# Relay.net
KiCad netlist of a schematic drawn in EAGLE
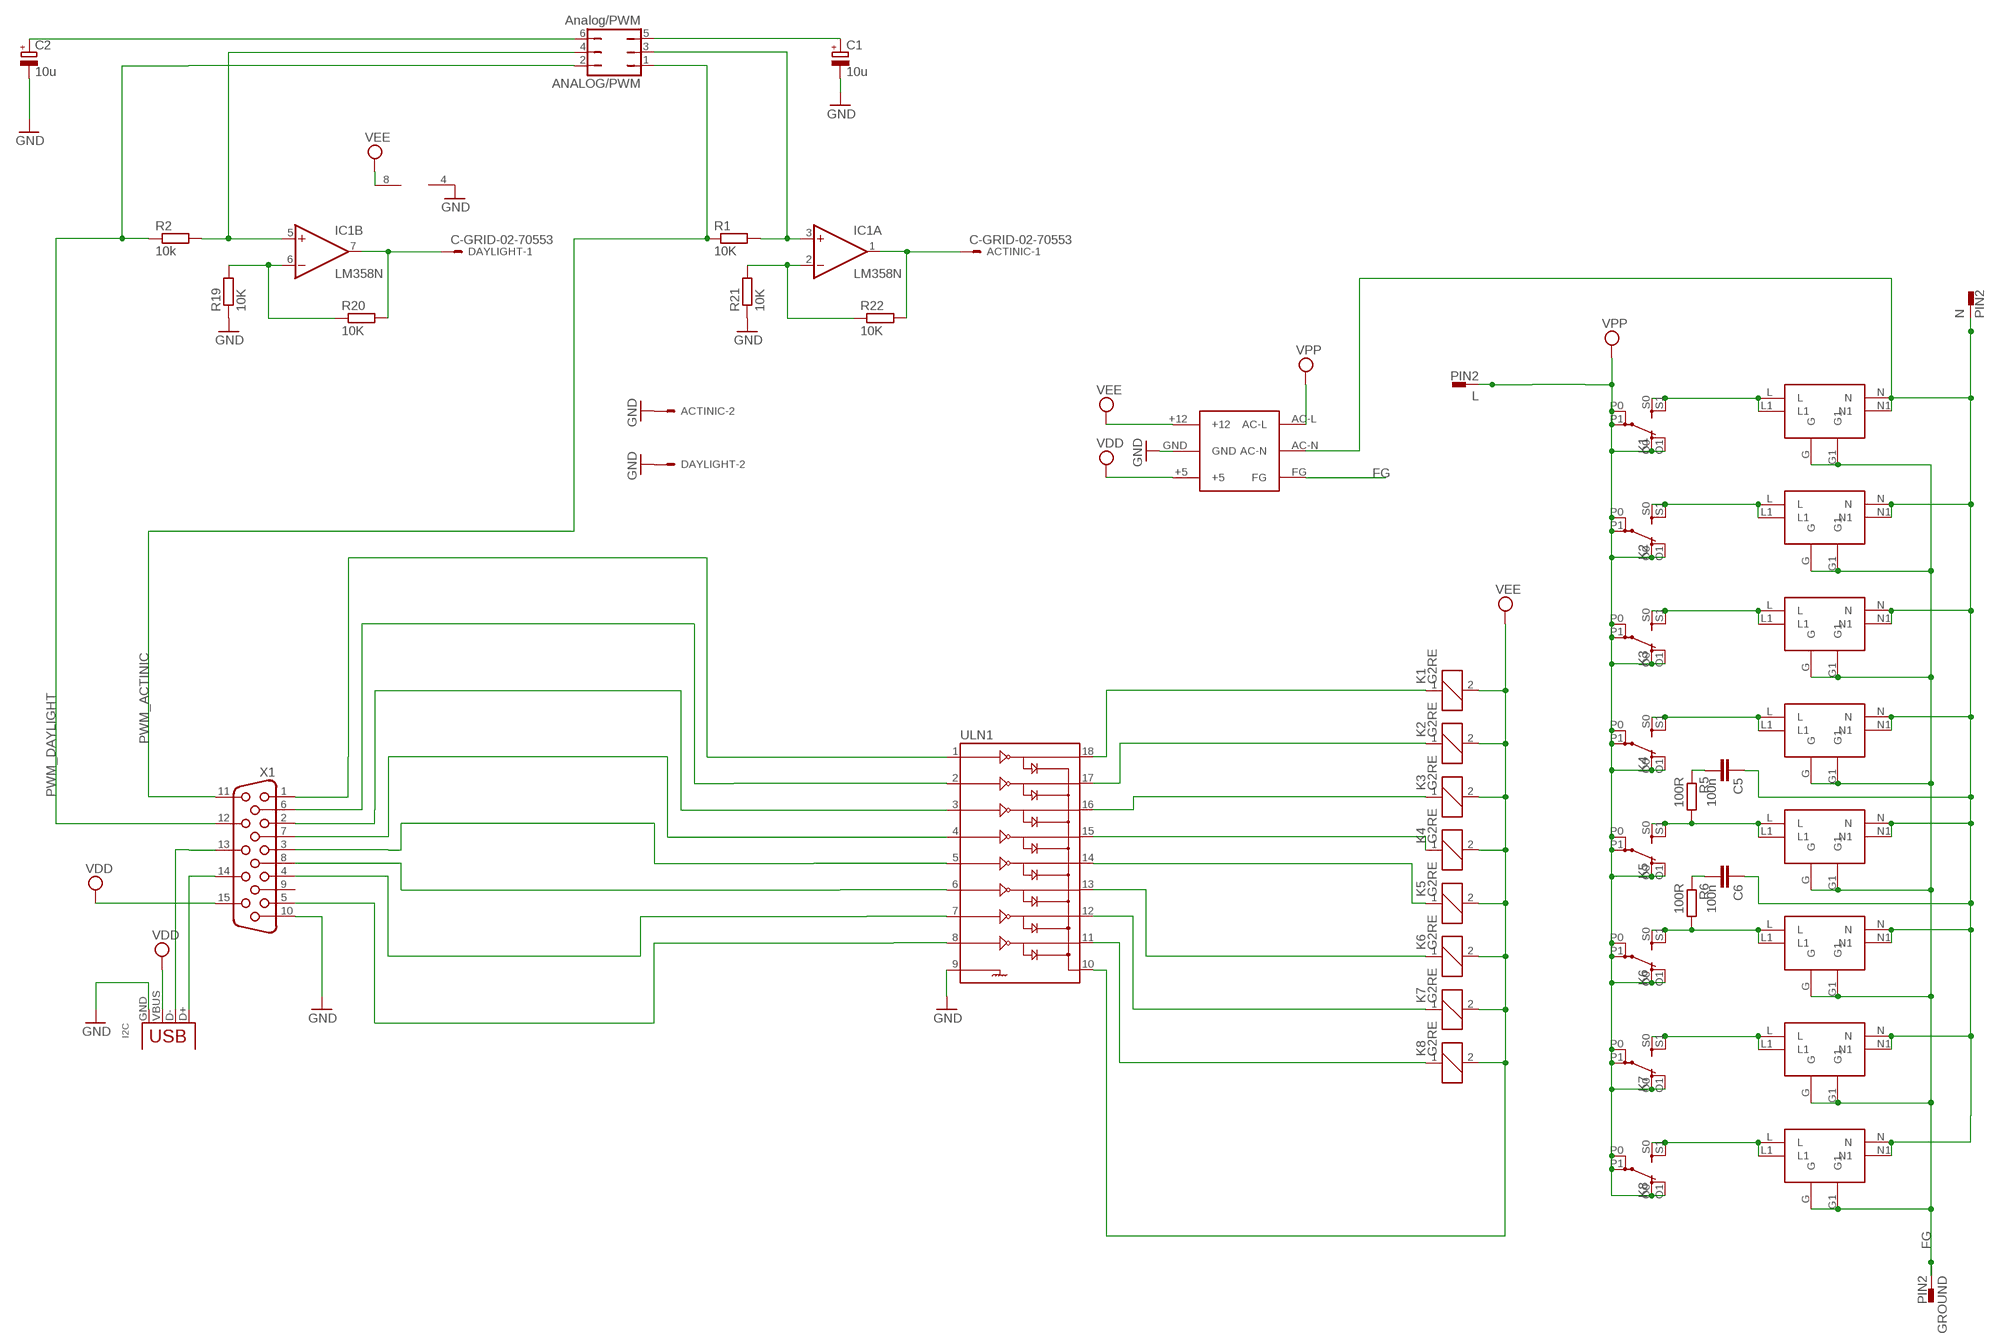
[diagram p0: schematic, sheet 1]

(export (version "E")
  (design (tool "Eeschema 10.0.6"))
  (components
    (comp (ref "ACTINIC")
      (value "C-GRID-02-70553")
      (footprint "eagle-import:70553-02")
      (libsource (lib "eagle-import") (part "C-GRID-02-70553"))
    )
    (comp (ref "ANALOG/PWM")
      (value "Analog/PWM")
      (footprint "eagle-import:JP3Q")
      (libsource (lib "eagle-import") (part "JP3Q"))
    )
    (comp (ref "C1")
      (value "10u")
      (footprint "eagle-import:E2-5")
      (libsource (lib "eagle-import") (part "CPOL-EUE2-5"))
    )
    (comp (ref "C2")
      (value "10u")
      (footprint "eagle-import:E2-5")
      (libsource (lib "eagle-import") (part "CPOL-EUE2-5"))
    )
    (comp (ref "C5")
      (value "100n")
      (footprint "eagle-import:C075-032X103")
      (libsource (lib "eagle-import") (part "C-EU075-032X103"))
    )
    (comp (ref "C6")
      (value "100n")
      (footprint "eagle-import:C075-032X103")
      (libsource (lib "eagle-import") (part "C-EU075-032X103"))
    )
    (comp (ref "DAYLIGHT")
      (value "C-GRID-02-70553")
      (footprint "eagle-import:70553-02")
      (libsource (lib "eagle-import") (part "C-GRID-02-70553"))
    )
    (comp (ref "GROUND")
      (value "PIN2")
      (footprint "eagle-import:F061.100-INLET")
      (libsource (lib "eagle-import") (part "PIN2"))
    )
    (comp (ref "I2C")
      (value "USB-A-H")
      (footprint "eagle-import:USB-A-H")
      (libsource (lib "eagle-import") (part "USB-A-H"))
    )
    (comp (ref "IC1")
      (value "LM358N")
      (footprint "eagle-import:DIL08")
      (libsource (lib "eagle-import") (part "LM358N"))
    )
    (comp (ref "K1")
      (value "G2RE")
      (footprint "eagle-import:G2RE")
      (libsource (lib "eagle-import") (part "G2RE"))
    )
    (comp (ref "K2")
      (value "G2RE")
      (footprint "eagle-import:G2RE")
      (libsource (lib "eagle-import") (part "G2RE"))
    )
    (comp (ref "K3")
      (value "G2RE")
      (footprint "eagle-import:G2RE")
      (libsource (lib "eagle-import") (part "G2RE"))
    )
    (comp (ref "K4")
      (value "G2RE")
      (footprint "eagle-import:G2RE")
      (libsource (lib "eagle-import") (part "G2RE"))
    )
    (comp (ref "K5")
      (value "G2RE")
      (footprint "eagle-import:G2RE")
      (libsource (lib "eagle-import") (part "G2RE"))
    )
    (comp (ref "K6")
      (value "G2RE")
      (footprint "eagle-import:G2RE")
      (libsource (lib "eagle-import") (part "G2RE"))
    )
    (comp (ref "K7")
      (value "G2RE")
      (footprint "eagle-import:G2RE")
      (libsource (lib "eagle-import") (part "G2RE"))
    )
    (comp (ref "K8")
      (value "G2RE")
      (footprint "eagle-import:G2RE")
      (libsource (lib "eagle-import") (part "G2RE"))
    )
    (comp (ref "L")
      (value "PIN2")
      (footprint "eagle-import:F061.100-INLET")
      (libsource (lib "eagle-import") (part "PIN2"))
    )
    (comp (ref "N")
      (value "PIN2")
      (footprint "eagle-import:F061.100-INLET")
      (libsource (lib "eagle-import") (part "PIN2"))
    )
    (comp (ref "O1")
      (value "SOCKET1")
      (footprint "eagle-import:SOCKET")
      (libsource (lib "eagle-import") (part "SOCKET1"))
    )
    (comp (ref "O2")
      (value "SOCKET1")
      (footprint "eagle-import:SOCKET")
      (libsource (lib "eagle-import") (part "SOCKET1"))
    )
    (comp (ref "O3")
      (value "SOCKET1")
      (footprint "eagle-import:SOCKET")
      (libsource (lib "eagle-import") (part "SOCKET1"))
    )
    (comp (ref "O4")
      (value "SOCKET1")
      (footprint "eagle-import:SOCKET")
      (libsource (lib "eagle-import") (part "SOCKET1"))
    )
    (comp (ref "O5")
      (value "SOCKET1")
      (footprint "eagle-import:SOCKET")
      (libsource (lib "eagle-import") (part "SOCKET1"))
    )
    (comp (ref "O6")
      (value "SOCKET1")
      (footprint "eagle-import:SOCKET")
      (libsource (lib "eagle-import") (part "SOCKET1"))
    )
    (comp (ref "O7")
      (value "SOCKET1")
      (footprint "eagle-import:SOCKET")
      (libsource (lib "eagle-import") (part "SOCKET1"))
    )
    (comp (ref "O8")
      (value "SOCKET1")
      (footprint "eagle-import:SOCKET")
      (libsource (lib "eagle-import") (part "SOCKET1"))
    )
    (comp (ref "PS1")
      (value "AC2200512DC")
      (footprint "eagle-import:AC2200512DC")
      (libsource (lib "eagle-import") (part "AC2200512DC"))
    )
    (comp (ref "R1")
      (value "10K")
      (footprint "eagle-import:0207_7")
      (libsource (lib "eagle-import") (part "R-EU_0207/7"))
    )
    (comp (ref "R2")
      (value "10k")
      (footprint "eagle-import:0207_7")
      (libsource (lib "eagle-import") (part "R-EU_0207/7"))
    )
    (comp (ref "R5")
      (value "100R")
      (footprint "eagle-import:0411_12")
      (libsource (lib "eagle-import") (part "R-EU_0411/12"))
    )
    (comp (ref "R6")
      (value "100R")
      (footprint "eagle-import:0411_12")
      (libsource (lib "eagle-import") (part "R-EU_0411/12"))
    )
    (comp (ref "R19")
      (value "10K")
      (footprint "eagle-import:0207_7")
      (libsource (lib "eagle-import") (part "R-EU_0207/7"))
    )
    (comp (ref "R20")
      (value "10K")
      (footprint "eagle-import:0207_7")
      (libsource (lib "eagle-import") (part "R-EU_0207/7"))
    )
    (comp (ref "R21")
      (value "10K")
      (footprint "eagle-import:0207_7")
      (libsource (lib "eagle-import") (part "R-EU_0207/7"))
    )
    (comp (ref "R22")
      (value "10K")
      (footprint "eagle-import:0207_7")
      (libsource (lib "eagle-import") (part "R-EU_0207/7"))
    )
    (comp (ref "ULN1")
      (value "ULN2803DIP")
      (footprint "eagle-import:DIL18")
      (libsource (lib "eagle-import") (part "ULN2803DIP"))
    )
    (comp (ref "X1")
      (value "HF15H")
      (footprint "eagle-import:HDF15H")
      (libsource (lib "eagle-import") (part "HF15H"))
    )
  )
  (nets
    (net (code "1") (name "/FG") (class "Default")
      (node (ref "GROUND") (pin "A1") (pinfunction "1_A1") (pintype "passive"))
      (node (ref "GROUND") (pin "A2") (pinfunction "1.1_A2") (pintype "passive"))
      (node (ref "O1") (pin "G") (pinfunction "G_G") (pintype "bidirectional"))
      (node (ref "O1") (pin "G1") (pinfunction "G1_G1") (pintype "bidirectional"))
      (node (ref "O2") (pin "G") (pinfunction "G_G") (pintype "bidirectional"))
      (node (ref "O2") (pin "G1") (pinfunction "G1_G1") (pintype "bidirectional"))
      (node (ref "O3") (pin "G") (pinfunction "G_G") (pintype "bidirectional"))
      (node (ref "O3") (pin "G1") (pinfunction "G1_G1") (pintype "bidirectional"))
      (node (ref "O4") (pin "G") (pinfunction "G_G") (pintype "bidirectional"))
      (node (ref "O4") (pin "G1") (pinfunction "G1_G1") (pintype "bidirectional"))
      (node (ref "O5") (pin "G") (pinfunction "G_G") (pintype "bidirectional"))
      (node (ref "O5") (pin "G1") (pinfunction "G1_G1") (pintype "bidirectional"))
      (node (ref "O6") (pin "G") (pinfunction "G_G") (pintype "bidirectional"))
      (node (ref "O6") (pin "G1") (pinfunction "G1_G1") (pintype "bidirectional"))
      (node (ref "O7") (pin "G") (pinfunction "G_G") (pintype "bidirectional"))
      (node (ref "O7") (pin "G1") (pinfunction "G1_G1") (pintype "bidirectional"))
      (node (ref "O8") (pin "G") (pinfunction "G_G") (pintype "bidirectional"))
      (node (ref "O8") (pin "G1") (pinfunction "G1_G1") (pintype "bidirectional"))
      (node (ref "PS1") (pin "FG") (pinfunction "FG_FG") (pintype "bidirectional"))
    )
    (net (code "2") (name "/PWM_ACTINIC") (class "Default")
      (node (ref "ANALOG/PWM") (pin "1") (pinfunction "1_1") (pintype "passive"))
      (node (ref "R1") (pin "1") (pinfunction "1_1") (pintype "passive"))
      (node (ref "X1") (pin "11") (pinfunction "11_11") (pintype "passive"))
    )
    (net (code "3") (name "/PWM_DAYLIGHT") (class "Default")
      (node (ref "ANALOG/PWM") (pin "2") (pinfunction "2_2") (pintype "passive"))
      (node (ref "R2") (pin "1") (pinfunction "1_1") (pintype "passive"))
      (node (ref "X1") (pin "12") (pinfunction "12_12") (pintype "passive"))
    )
    (net (code "4") (name "GND") (class "Default")
      (node (ref "ACTINIC") (pin "2") (pinfunction "S_2") (pintype "passive"))
      (node (ref "C1") (pin "-") (pinfunction "-_-") (pintype "passive"))
      (node (ref "C2") (pin "-") (pinfunction "-_-") (pintype "passive"))
      (node (ref "DAYLIGHT") (pin "2") (pinfunction "S_2") (pintype "passive"))
      (node (ref "I2C") (pin "GND") (pinfunction "GND_GND") (pintype "bidirectional"))
      (node (ref "IC1") (pin "4") (pinfunction "V-_4") (pintype "power_in"))
      (node (ref "PS1") (pin "GND") (pinfunction "GND_GND") (pintype "bidirectional"))
      (node (ref "R19") (pin "1") (pinfunction "1_1") (pintype "passive"))
      (node (ref "R21") (pin "1") (pinfunction "1_1") (pintype "passive"))
      (node (ref "ULN1") (pin "9") (pinfunction "9_9") (pintype "bidirectional"))
      (node (ref "X1") (pin "10") (pinfunction "10_10") (pintype "passive"))
    )
    (net (code "5") (name "Net-(ACTINICA-S)") (class "Default")
      (node (ref "ACTINIC") (pin "1") (pinfunction "S_1") (pintype "passive"))
      (node (ref "IC1") (pin "1") (pinfunction "OUT_1") (pintype "output"))
      (node (ref "R22") (pin "2") (pinfunction "2_2") (pintype "passive"))
    )
    (net (code "6") (name "Net-(ANALOG/PWM-Pad5)") (class "Default")
      (node (ref "ANALOG/PWM") (pin "5") (pinfunction "5_5") (pintype "passive"))
      (node (ref "C1") (pin "+") (pinfunction "+_+") (pintype "passive"))
    )
    (net (code "7") (name "Net-(ANALOG/PWM-Pad6)") (class "Default")
      (node (ref "ANALOG/PWM") (pin "6") (pinfunction "6_6") (pintype "passive"))
      (node (ref "C2") (pin "+") (pinfunction "+_+") (pintype "passive"))
    )
    (net (code "8") (name "Net-(C5-Pad2)") (class "Default")
      (node (ref "C5") (pin "2") (pinfunction "2_2") (pintype "passive"))
      (node (ref "R5") (pin "1") (pinfunction "1_1") (pintype "passive"))
    )
    (net (code "9") (name "Net-(C6-Pad2)") (class "Default")
      (node (ref "C6") (pin "2") (pinfunction "2_2") (pintype "passive"))
      (node (ref "R6") (pin "1") (pinfunction "1_1") (pintype "passive"))
    )
    (net (code "10") (name "Net-(DAYLIGHTA-S)") (class "Default")
      (node (ref "DAYLIGHT") (pin "1") (pinfunction "S_1") (pintype "passive"))
      (node (ref "IC1") (pin "7") (pinfunction "OUT_7") (pintype "output"))
      (node (ref "R20") (pin "2") (pinfunction "2_2") (pintype "passive"))
    )
    (net (code "11") (name "Net-(I2C-PadD+)") (class "Default")
      (node (ref "I2C") (pin "D+") (pinfunction "D+_D+") (pintype "bidirectional"))
      (node (ref "X1") (pin "14") (pinfunction "14_14") (pintype "passive"))
    )
    (net (code "12") (name "Net-(I2C-PadD-)") (class "Default")
      (node (ref "I2C") (pin "D-") (pinfunction "D-_D-") (pintype "bidirectional"))
      (node (ref "X1") (pin "13") (pinfunction "13_13") (pintype "passive"))
    )
    (net (code "13") (name "Net-(IC1A-+IN)") (class "Default")
      (node (ref "ANALOG/PWM") (pin "3") (pinfunction "3_3") (pintype "passive"))
      (node (ref "IC1") (pin "3") (pinfunction "+IN_3") (pintype "input"))
      (node (ref "R1") (pin "2") (pinfunction "2_2") (pintype "passive"))
    )
    (net (code "14") (name "Net-(IC1A--IN)") (class "Default")
      (node (ref "IC1") (pin "2") (pinfunction "-IN_2") (pintype "input"))
      (node (ref "R21") (pin "2") (pinfunction "2_2") (pintype "passive"))
      (node (ref "R22") (pin "1") (pinfunction "1_1") (pintype "passive"))
    )
    (net (code "15") (name "Net-(IC1B-+IN)") (class "Default")
      (node (ref "ANALOG/PWM") (pin "4") (pinfunction "4_4") (pintype "passive"))
      (node (ref "IC1") (pin "5") (pinfunction "+IN_5") (pintype "input"))
      (node (ref "R2") (pin "2") (pinfunction "2_2") (pintype "passive"))
    )
    (net (code "16") (name "Net-(IC1B--IN)") (class "Default")
      (node (ref "IC1") (pin "6") (pinfunction "-IN_6") (pintype "input"))
      (node (ref "R19") (pin "2") (pinfunction "2_2") (pintype "passive"))
      (node (ref "R20") (pin "1") (pinfunction "1_1") (pintype "passive"))
    )
    (net (code "17") (name "Net-(K1-Pad1)") (class "Default")
      (node (ref "K1") (pin "1") (pinfunction "1_1") (pintype "passive"))
      (node (ref "ULN1") (pin "18") (pinfunction "18_18") (pintype "bidirectional"))
    )
    (net (code "18") (name "Net-(K1B-S-PadS0)") (class "Default")
      (node (ref "K1") (pin "S0") (pinfunction "S_S0") (pintype "passive"))
      (node (ref "K1") (pin "S1") (pinfunction "S_S1") (pintype "passive"))
      (node (ref "O1") (pin "L") (pinfunction "L_L") (pintype "bidirectional"))
      (node (ref "O1") (pin "L1") (pinfunction "L1_L1") (pintype "bidirectional"))
    )
    (net (code "19") (name "Net-(K2-Pad1)") (class "Default")
      (node (ref "K2") (pin "1") (pinfunction "1_1") (pintype "passive"))
      (node (ref "ULN1") (pin "17") (pinfunction "17_17") (pintype "bidirectional"))
    )
    (net (code "20") (name "Net-(K2B-S-PadS0)") (class "Default")
      (node (ref "K2") (pin "S0") (pinfunction "S_S0") (pintype "passive"))
      (node (ref "K2") (pin "S1") (pinfunction "S_S1") (pintype "passive"))
      (node (ref "O2") (pin "L") (pinfunction "L_L") (pintype "bidirectional"))
      (node (ref "O2") (pin "L1") (pinfunction "L1_L1") (pintype "bidirectional"))
    )
    (net (code "21") (name "Net-(K3-Pad1)") (class "Default")
      (node (ref "K3") (pin "1") (pinfunction "1_1") (pintype "passive"))
      (node (ref "ULN1") (pin "16") (pinfunction "16_16") (pintype "bidirectional"))
    )
    (net (code "22") (name "Net-(K3B-S-PadS0)") (class "Default")
      (node (ref "K3") (pin "S0") (pinfunction "S_S0") (pintype "passive"))
      (node (ref "K3") (pin "S1") (pinfunction "S_S1") (pintype "passive"))
      (node (ref "O3") (pin "L") (pinfunction "L_L") (pintype "bidirectional"))
      (node (ref "O3") (pin "L1") (pinfunction "L1_L1") (pintype "bidirectional"))
    )
    (net (code "23") (name "Net-(K4-Pad1)") (class "Default")
      (node (ref "K4") (pin "1") (pinfunction "1_1") (pintype "passive"))
      (node (ref "ULN1") (pin "15") (pinfunction "15_15") (pintype "bidirectional"))
    )
    (net (code "24") (name "Net-(K4B-S-PadS0)") (class "Default")
      (node (ref "K4") (pin "S0") (pinfunction "S_S0") (pintype "passive"))
      (node (ref "K4") (pin "S1") (pinfunction "S_S1") (pintype "passive"))
      (node (ref "O4") (pin "L") (pinfunction "L_L") (pintype "bidirectional"))
      (node (ref "O4") (pin "L1") (pinfunction "L1_L1") (pintype "bidirectional"))
    )
    (net (code "25") (name "Net-(K5-Pad1)") (class "Default")
      (node (ref "K5") (pin "1") (pinfunction "1_1") (pintype "passive"))
      (node (ref "ULN1") (pin "14") (pinfunction "14_14") (pintype "bidirectional"))
    )
    (net (code "26") (name "Net-(K5B-S-PadS0)") (class "Default")
      (node (ref "K5") (pin "S0") (pinfunction "S_S0") (pintype "passive"))
      (node (ref "K5") (pin "S1") (pinfunction "S_S1") (pintype "passive"))
      (node (ref "O5") (pin "L") (pinfunction "L_L") (pintype "bidirectional"))
      (node (ref "O5") (pin "L1") (pinfunction "L1_L1") (pintype "bidirectional"))
      (node (ref "R5") (pin "2") (pinfunction "2_2") (pintype "passive"))
    )
    (net (code "27") (name "Net-(K6-Pad1)") (class "Default")
      (node (ref "K6") (pin "1") (pinfunction "1_1") (pintype "passive"))
      (node (ref "ULN1") (pin "13") (pinfunction "13_13") (pintype "bidirectional"))
    )
    (net (code "28") (name "Net-(K6B-S-PadS0)") (class "Default")
      (node (ref "K6") (pin "S0") (pinfunction "S_S0") (pintype "passive"))
      (node (ref "K6") (pin "S1") (pinfunction "S_S1") (pintype "passive"))
      (node (ref "O6") (pin "L") (pinfunction "L_L") (pintype "bidirectional"))
      (node (ref "O6") (pin "L1") (pinfunction "L1_L1") (pintype "bidirectional"))
      (node (ref "R6") (pin "2") (pinfunction "2_2") (pintype "passive"))
    )
    (net (code "29") (name "Net-(K7-Pad1)") (class "Default")
      (node (ref "K7") (pin "1") (pinfunction "1_1") (pintype "passive"))
      (node (ref "ULN1") (pin "12") (pinfunction "12_12") (pintype "bidirectional"))
    )
    (net (code "30") (name "Net-(K7B-S-PadS0)") (class "Default")
      (node (ref "K7") (pin "S0") (pinfunction "S_S0") (pintype "passive"))
      (node (ref "K7") (pin "S1") (pinfunction "S_S1") (pintype "passive"))
      (node (ref "O7") (pin "L") (pinfunction "L_L") (pintype "bidirectional"))
      (node (ref "O7") (pin "L1") (pinfunction "L1_L1") (pintype "bidirectional"))
    )
    (net (code "31") (name "Net-(K8-Pad1)") (class "Default")
      (node (ref "K8") (pin "1") (pinfunction "1_1") (pintype "passive"))
      (node (ref "ULN1") (pin "11") (pinfunction "11_11") (pintype "bidirectional"))
    )
    (net (code "32") (name "Net-(K8B-S-PadS0)") (class "Default")
      (node (ref "K8") (pin "S0") (pinfunction "S_S0") (pintype "passive"))
      (node (ref "K8") (pin "S1") (pinfunction "S_S1") (pintype "passive"))
      (node (ref "O8") (pin "L") (pinfunction "L_L") (pintype "bidirectional"))
      (node (ref "O8") (pin "L1") (pinfunction "L1_L1") (pintype "bidirectional"))
    )
    (net (code "33") (name "Net-(N-1)") (class "Default")
      (node (ref "C5") (pin "1") (pinfunction "1_1") (pintype "passive"))
      (node (ref "C6") (pin "1") (pinfunction "1_1") (pintype "passive"))
      (node (ref "N") (pin "A1") (pinfunction "1_A1") (pintype "passive"))
      (node (ref "N") (pin "A2") (pinfunction "1.1_A2") (pintype "passive"))
      (node (ref "O1") (pin "N") (pinfunction "N_N") (pintype "bidirectional"))
      (node (ref "O1") (pin "N1") (pinfunction "N1_N1") (pintype "bidirectional"))
      (node (ref "O2") (pin "N") (pinfunction "N_N") (pintype "bidirectional"))
      (node (ref "O2") (pin "N1") (pinfunction "N1_N1") (pintype "bidirectional"))
      (node (ref "O3") (pin "N") (pinfunction "N_N") (pintype "bidirectional"))
      (node (ref "O3") (pin "N1") (pinfunction "N1_N1") (pintype "bidirectional"))
      (node (ref "O4") (pin "N") (pinfunction "N_N") (pintype "bidirectional"))
      (node (ref "O4") (pin "N1") (pinfunction "N1_N1") (pintype "bidirectional"))
      (node (ref "O5") (pin "N") (pinfunction "N_N") (pintype "bidirectional"))
      (node (ref "O5") (pin "N1") (pinfunction "N1_N1") (pintype "bidirectional"))
      (node (ref "O6") (pin "N") (pinfunction "N_N") (pintype "bidirectional"))
      (node (ref "O6") (pin "N1") (pinfunction "N1_N1") (pintype "bidirectional"))
      (node (ref "O7") (pin "N") (pinfunction "N_N") (pintype "bidirectional"))
      (node (ref "O7") (pin "N1") (pinfunction "N1_N1") (pintype "bidirectional"))
      (node (ref "O8") (pin "N") (pinfunction "N_N") (pintype "bidirectional"))
      (node (ref "O8") (pin "N1") (pinfunction "N1_N1") (pintype "bidirectional"))
      (node (ref "PS1") (pin "AC-N") (pinfunction "AC-N_AC-N") (pintype "bidirectional"))
    )
    (net (code "34") (name "Net-(ULN1-Pad1)") (class "Default")
      (node (ref "ULN1") (pin "1") (pinfunction "1_1") (pintype "bidirectional"))
      (node (ref "X1") (pin "1") (pinfunction "1_1") (pintype "passive"))
    )
    (net (code "35") (name "Net-(ULN1-Pad2)") (class "Default")
      (node (ref "ULN1") (pin "2") (pinfunction "2_2") (pintype "bidirectional"))
      (node (ref "X1") (pin "6") (pinfunction "6_6") (pintype "passive"))
    )
    (net (code "36") (name "Net-(ULN1-Pad3)") (class "Default")
      (node (ref "ULN1") (pin "3") (pinfunction "3_3") (pintype "bidirectional"))
      (node (ref "X1") (pin "2") (pinfunction "2_2") (pintype "passive"))
    )
    (net (code "37") (name "Net-(ULN1-Pad4)") (class "Default")
      (node (ref "ULN1") (pin "4") (pinfunction "4_4") (pintype "bidirectional"))
      (node (ref "X1") (pin "7") (pinfunction "7_7") (pintype "passive"))
    )
    (net (code "38") (name "Net-(ULN1-Pad5)") (class "Default")
      (node (ref "ULN1") (pin "5") (pinfunction "5_5") (pintype "bidirectional"))
      (node (ref "X1") (pin "3") (pinfunction "3_3") (pintype "passive"))
    )
    (net (code "39") (name "Net-(ULN1-Pad6)") (class "Default")
      (node (ref "ULN1") (pin "6") (pinfunction "6_6") (pintype "bidirectional"))
      (node (ref "X1") (pin "8") (pinfunction "8_8") (pintype "passive"))
    )
    (net (code "40") (name "Net-(ULN1-Pad7)") (class "Default")
      (node (ref "ULN1") (pin "7") (pinfunction "7_7") (pintype "bidirectional"))
      (node (ref "X1") (pin "4") (pinfunction "4_4") (pintype "passive"))
    )
    (net (code "41") (name "Net-(ULN1-Pad8)") (class "Default")
      (node (ref "ULN1") (pin "8") (pinfunction "8_8") (pintype "bidirectional"))
      (node (ref "X1") (pin "5") (pinfunction "5_5") (pintype "passive"))
    )
    (net (code "42") (name "VDD") (class "Default")
      (node (ref "I2C") (pin "VBUS") (pinfunction "VBUS_VBUS") (pintype "bidirectional"))
      (node (ref "PS1") (pin "+5") (pinfunction "+5_+5") (pintype "bidirectional"))
      (node (ref "X1") (pin "15") (pinfunction "15_15") (pintype "passive"))
    )
    (net (code "43") (name "VEE") (class "Default")
      (node (ref "IC1") (pin "8") (pinfunction "V+_8") (pintype "power_in"))
      (node (ref "K1") (pin "2") (pinfunction "2_2") (pintype "passive"))
      (node (ref "K2") (pin "2") (pinfunction "2_2") (pintype "passive"))
      (node (ref "K3") (pin "2") (pinfunction "2_2") (pintype "passive"))
      (node (ref "K4") (pin "2") (pinfunction "2_2") (pintype "passive"))
      (node (ref "K5") (pin "2") (pinfunction "2_2") (pintype "passive"))
      (node (ref "K6") (pin "2") (pinfunction "2_2") (pintype "passive"))
      (node (ref "K7") (pin "2") (pinfunction "2_2") (pintype "passive"))
      (node (ref "K8") (pin "2") (pinfunction "2_2") (pintype "passive"))
      (node (ref "PS1") (pin "+12") (pinfunction "+12_+12") (pintype "bidirectional"))
      (node (ref "ULN1") (pin "10") (pinfunction "10_10") (pintype "bidirectional"))
    )
    (net (code "44") (name "VPP") (class "Default")
      (node (ref "K1") (pin "O0") (pinfunction "O_O0") (pintype "passive"))
      (node (ref "K1") (pin "O1") (pinfunction "O_O1") (pintype "passive"))
      (node (ref "K1") (pin "P0") (pinfunction "P_P0") (pintype "passive"))
      (node (ref "K1") (pin "P1") (pinfunction "P_P1") (pintype "passive"))
      (node (ref "K2") (pin "O0") (pinfunction "O_O0") (pintype "passive"))
      (node (ref "K2") (pin "O1") (pinfunction "O_O1") (pintype "passive"))
      (node (ref "K2") (pin "P0") (pinfunction "P_P0") (pintype "passive"))
      (node (ref "K2") (pin "P1") (pinfunction "P_P1") (pintype "passive"))
      (node (ref "K3") (pin "O0") (pinfunction "O_O0") (pintype "passive"))
      (node (ref "K3") (pin "O1") (pinfunction "O_O1") (pintype "passive"))
      (node (ref "K3") (pin "P0") (pinfunction "P_P0") (pintype "passive"))
      (node (ref "K3") (pin "P1") (pinfunction "P_P1") (pintype "passive"))
      (node (ref "K4") (pin "O0") (pinfunction "O_O0") (pintype "passive"))
      (node (ref "K4") (pin "O1") (pinfunction "O_O1") (pintype "passive"))
      (node (ref "K4") (pin "P0") (pinfunction "P_P0") (pintype "passive"))
      (node (ref "K4") (pin "P1") (pinfunction "P_P1") (pintype "passive"))
      (node (ref "K5") (pin "O0") (pinfunction "O_O0") (pintype "passive"))
      (node (ref "K5") (pin "O1") (pinfunction "O_O1") (pintype "passive"))
      (node (ref "K5") (pin "P0") (pinfunction "P_P0") (pintype "passive"))
      (node (ref "K5") (pin "P1") (pinfunction "P_P1") (pintype "passive"))
      (node (ref "K6") (pin "O0") (pinfunction "O_O0") (pintype "passive"))
      (node (ref "K6") (pin "O1") (pinfunction "O_O1") (pintype "passive"))
      (node (ref "K6") (pin "P0") (pinfunction "P_P0") (pintype "passive"))
      (node (ref "K6") (pin "P1") (pinfunction "P_P1") (pintype "passive"))
      (node (ref "K7") (pin "O0") (pinfunction "O_O0") (pintype "passive"))
      (node (ref "K7") (pin "O1") (pinfunction "O_O1") (pintype "passive"))
      (node (ref "K7") (pin "P0") (pinfunction "P_P0") (pintype "passive"))
      (node (ref "K7") (pin "P1") (pinfunction "P_P1") (pintype "passive"))
      (node (ref "K8") (pin "O0") (pinfunction "O_O0") (pintype "passive"))
      (node (ref "K8") (pin "O1") (pinfunction "O_O1") (pintype "passive"))
      (node (ref "K8") (pin "P0") (pinfunction "P_P0") (pintype "passive"))
      (node (ref "K8") (pin "P1") (pinfunction "P_P1") (pintype "passive"))
      (node (ref "L") (pin "A1") (pinfunction "1_A1") (pintype "passive"))
      (node (ref "L") (pin "A2") (pinfunction "1.1_A2") (pintype "passive"))
      (node (ref "PS1") (pin "AC-L") (pinfunction "AC-L_AC-L") (pintype "bidirectional"))
    )
    (net (code "45") (name "unconnected-(X1-Pad9)") (class "Default")
      (node (ref "X1") (pin "9") (pinfunction "9_9") (pintype "passive"))
    )
  )
)
